# main.net
KiCad netlist of a schematic drawn in EAGLE
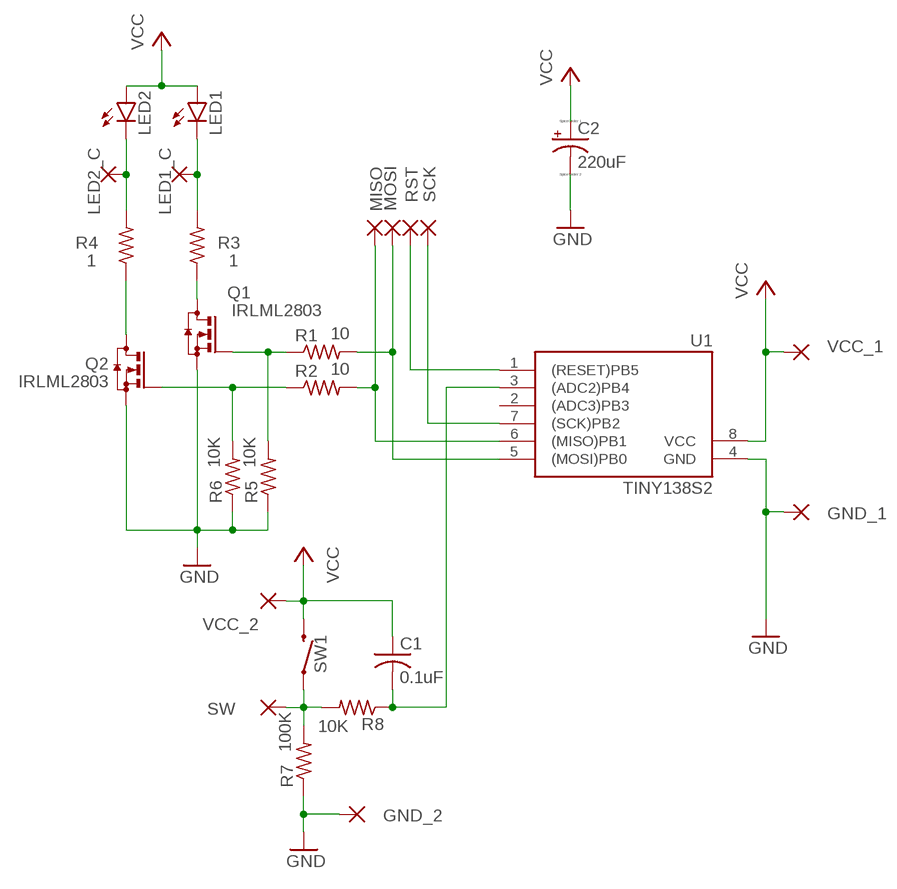
[diagram p0: schematic, sheet 1]

(export (version "E")
  (design (tool "Eeschema 10.0.6"))
  (components
    (comp (ref "C1")
      (value "0.1uF")
      (footprint "eagle-import:C0805")
      (libsource (lib "eagle-import") (part "C-USC0805"))
    )
    (comp (ref "C2")
      (value "220uF")
      (footprint "eagle-import:E2,5-6E")
      (libsource (lib "eagle-import") (part "CPOL-USE2,5-6E"))
    )
    (comp (ref "GND_1")
      (value "1,6/0,9")
      (footprint "eagle-import:1,6_0,9")
      (libsource (lib "eagle-import") (part "1,6/0,9"))
    )
    (comp (ref "GND_2")
      (value "1,6/0,9")
      (footprint "eagle-import:1,6_0,9")
      (libsource (lib "eagle-import") (part "1,6/0,9"))
    )
    (comp (ref "LED1")
      (value "Z-POWER-LED")
      (footprint "eagle-import:Z-POWER-LED-PCB-TYPE")
      (libsource (lib "eagle-import") (part "Z-POWER-LED"))
    )
    (comp (ref "LED1_C")
      (value "1,6/0,9")
      (footprint "eagle-import:1,6_0,9")
      (libsource (lib "eagle-import") (part "1,6/0,9"))
    )
    (comp (ref "LED2")
      (value "Z-POWER-LED")
      (footprint "eagle-import:Z-POWER-LED-PCB-TYPE")
      (libsource (lib "eagle-import") (part "Z-POWER-LED"))
    )
    (comp (ref "LED2_C")
      (value "1,6/0,9")
      (footprint "eagle-import:1,6_0,9")
      (libsource (lib "eagle-import") (part "1,6/0,9"))
    )
    (comp (ref "MISO")
      (value "1,6/0,9")
      (footprint "eagle-import:1,6_0,9")
      (libsource (lib "eagle-import") (part "1,6/0,9"))
    )
    (comp (ref "MOSI")
      (value "1,6/0,9")
      (footprint "eagle-import:1,6_0,9")
      (libsource (lib "eagle-import") (part "1,6/0,9"))
    )
    (comp (ref "Q1")
      (value "IRLML2803")
      (footprint "eagle-import:SOT23")
      (libsource (lib "eagle-import") (part "IRLML2803"))
    )
    (comp (ref "Q2")
      (value "IRLML2803")
      (footprint "eagle-import:SOT23")
      (libsource (lib "eagle-import") (part "IRLML2803"))
    )
    (comp (ref "R1")
      (value "10")
      (footprint "eagle-import:R0805")
      (libsource (lib "eagle-import") (part "R-US_R0805"))
    )
    (comp (ref "R2")
      (value "10")
      (footprint "eagle-import:R0805")
      (libsource (lib "eagle-import") (part "R-US_R0805"))
    )
    (comp (ref "R3")
      (value "1")
      (footprint "eagle-import:0309_10")
      (libsource (lib "eagle-import") (part "R-US_0309/10"))
    )
    (comp (ref "R4")
      (value "1")
      (footprint "eagle-import:0309_10")
      (libsource (lib "eagle-import") (part "R-US_0309/10"))
    )
    (comp (ref "R5")
      (value "10K")
      (footprint "eagle-import:R0805")
      (libsource (lib "eagle-import") (part "R-US_R0805"))
    )
    (comp (ref "R6")
      (value "10K")
      (footprint "eagle-import:R0805")
      (libsource (lib "eagle-import") (part "R-US_R0805"))
    )
    (comp (ref "R7")
      (value "100K")
      (footprint "eagle-import:R0805")
      (libsource (lib "eagle-import") (part "R-US_R0805"))
    )
    (comp (ref "R8")
      (value "10K")
      (footprint "eagle-import:R0805")
      (libsource (lib "eagle-import") (part "R-US_R0805"))
    )
    (comp (ref "RST")
      (value "1,6/0,9")
      (footprint "eagle-import:1,6_0,9")
      (libsource (lib "eagle-import") (part "1,6/0,9"))
    )
    (comp (ref "SCK")
      (value "1,6/0,9")
      (footprint "eagle-import:1,6_0,9")
      (libsource (lib "eagle-import") (part "1,6/0,9"))
    )
    (comp (ref "SW")
      (value "1,6/0,9")
      (footprint "eagle-import:1,6_0,9")
      (libsource (lib "eagle-import") (part "1,6/0,9"))
    )
    (comp (ref "SW1")
      (value "MOMENTARY-SWITCH-SPST-PTH-6.0MM")
      (footprint "eagle-import:TACTILE_SWITCH_PTH_6.0MM")
      (libsource (lib "eagle-import") (part "MOMENTARY-SWITCH-SPST-PTH-6.0MM"))
    )
    (comp (ref "U1")
      (value "TINY138S2")
      (footprint "eagle-import:SO08")
      (libsource (lib "eagle-import") (part "TINY138S2"))
    )
    (comp (ref "VCC_1")
      (value "1,6/0,9")
      (footprint "eagle-import:1,6_0,9")
      (libsource (lib "eagle-import") (part "1,6/0,9"))
    )
    (comp (ref "VCC_2")
      (value "1,6/0,9")
      (footprint "eagle-import:1,6_0,9")
      (libsource (lib "eagle-import") (part "1,6/0,9"))
    )
  )
  (nets
    (net (code "1") (name "GND") (class "Default")
      (node (ref "C2") (pin "-") (pinfunction "-_-") (pintype "passive"))
      (node (ref "GND_1") (pin "1") (pinfunction "P_1") (pintype "passive"))
      (node (ref "GND_2") (pin "1") (pinfunction "P_1") (pintype "passive"))
      (node (ref "Q1") (pin "2") (pinfunction "S_2") (pintype "passive"))
      (node (ref "Q2") (pin "2") (pinfunction "S_2") (pintype "passive"))
      (node (ref "R5") (pin "1") (pinfunction "1_1") (pintype "passive"))
      (node (ref "R6") (pin "1") (pinfunction "1_1") (pintype "passive"))
      (node (ref "R7") (pin "1") (pinfunction "1_1") (pintype "passive"))
      (node (ref "U1") (pin "4") (pinfunction "GND_4") (pintype "power_in"))
    )
    (net (code "2") (name "Net-(LED1_C-P)") (class "Default")
      (node (ref "LED1") (pin "C") (pinfunction "C_C") (pintype "passive"))
      (node (ref "LED1_C") (pin "1") (pinfunction "P_1") (pintype "passive"))
      (node (ref "R3") (pin "2") (pinfunction "2_2") (pintype "passive"))
    )
    (net (code "3") (name "Net-(LED2_C-P)") (class "Default")
      (node (ref "LED2") (pin "C") (pinfunction "C_C") (pintype "passive"))
      (node (ref "LED2_C") (pin "1") (pinfunction "P_1") (pintype "passive"))
      (node (ref "R4") (pin "2") (pinfunction "2_2") (pintype "passive"))
    )
    (net (code "4") (name "Net-(MISO-P)") (class "Default")
      (node (ref "MISO") (pin "1") (pinfunction "P_1") (pintype "passive"))
      (node (ref "R2") (pin "2") (pinfunction "2_2") (pintype "passive"))
      (node (ref "U1") (pin "6") (pinfunction "(MISO)PB1_6") (pintype "bidirectional"))
    )
    (net (code "5") (name "Net-(MOSI-P)") (class "Default")
      (node (ref "MOSI") (pin "1") (pinfunction "P_1") (pintype "passive"))
      (node (ref "R1") (pin "2") (pinfunction "2_2") (pintype "passive"))
      (node (ref "U1") (pin "5") (pinfunction "(MOSI)PB0_5") (pintype "bidirectional"))
    )
    (net (code "6") (name "Net-(Q1-D)") (class "Default")
      (node (ref "Q1") (pin "3") (pinfunction "D_3") (pintype "passive"))
      (node (ref "R3") (pin "1") (pinfunction "1_1") (pintype "passive"))
    )
    (net (code "7") (name "Net-(Q1-G)") (class "Default")
      (node (ref "Q1") (pin "1") (pinfunction "G_1") (pintype "passive"))
      (node (ref "R1") (pin "1") (pinfunction "1_1") (pintype "passive"))
      (node (ref "R5") (pin "2") (pinfunction "2_2") (pintype "passive"))
    )
    (net (code "8") (name "Net-(Q2-D)") (class "Default")
      (node (ref "Q2") (pin "3") (pinfunction "D_3") (pintype "passive"))
      (node (ref "R4") (pin "1") (pinfunction "1_1") (pintype "passive"))
    )
    (net (code "9") (name "Net-(Q2-G)") (class "Default")
      (node (ref "Q2") (pin "1") (pinfunction "G_1") (pintype "passive"))
      (node (ref "R2") (pin "1") (pinfunction "1_1") (pintype "passive"))
      (node (ref "R6") (pin "2") (pinfunction "2_2") (pintype "passive"))
    )
    (net (code "10") (name "Net-(RST-P)") (class "Default")
      (node (ref "RST") (pin "1") (pinfunction "P_1") (pintype "passive"))
      (node (ref "U1") (pin "1") (pinfunction "(RESET)PB5_1") (pintype "bidirectional"))
    )
    (net (code "11") (name "Net-(SCK-P)") (class "Default")
      (node (ref "SCK") (pin "1") (pinfunction "P_1") (pintype "passive"))
      (node (ref "U1") (pin "7") (pinfunction "(SCK)PB2_7") (pintype "bidirectional"))
    )
    (net (code "12") (name "Net-(SW-P)") (class "Default")
      (node (ref "R7") (pin "2") (pinfunction "2_2") (pintype "passive"))
      (node (ref "R8") (pin "2") (pinfunction "2_2") (pintype "passive"))
      (node (ref "SW") (pin "1") (pinfunction "P_1") (pintype "passive"))
      (node (ref "SW1") (pin "1") (pinfunction "1_1") (pintype "passive"))
    )
    (net (code "13") (name "Net-(U1-(ADC2)PB4)") (class "Default")
      (node (ref "C1") (pin "2") (pinfunction "2_2") (pintype "passive"))
      (node (ref "R8") (pin "1") (pinfunction "1_1") (pintype "passive"))
      (node (ref "U1") (pin "3") (pinfunction "(ADC2)PB4_3") (pintype "bidirectional"))
    )
    (net (code "14") (name "VCC") (class "Default")
      (node (ref "C1") (pin "1") (pinfunction "1_1") (pintype "passive"))
      (node (ref "C2") (pin "+") (pinfunction "+_+") (pintype "passive"))
      (node (ref "LED1") (pin "A") (pinfunction "A_A") (pintype "passive"))
      (node (ref "LED2") (pin "A") (pinfunction "A_A") (pintype "passive"))
      (node (ref "SW1") (pin "3") (pinfunction "2_3") (pintype "passive"))
      (node (ref "U1") (pin "8") (pinfunction "VCC_8") (pintype "power_in"))
      (node (ref "VCC_1") (pin "1") (pinfunction "P_1") (pintype "passive"))
      (node (ref "VCC_2") (pin "1") (pinfunction "P_1") (pintype "passive"))
    )
    (net (code "15") (name "unconnected-(U1-(ADC3)PB3-Pad2)") (class "Default")
      (node (ref "U1") (pin "2") (pinfunction "(ADC3)PB3_2") (pintype "bidirectional"))
    )
  )
)
